# M710-9601.net
KiCad netlist of a schematic drawn in EAGLE
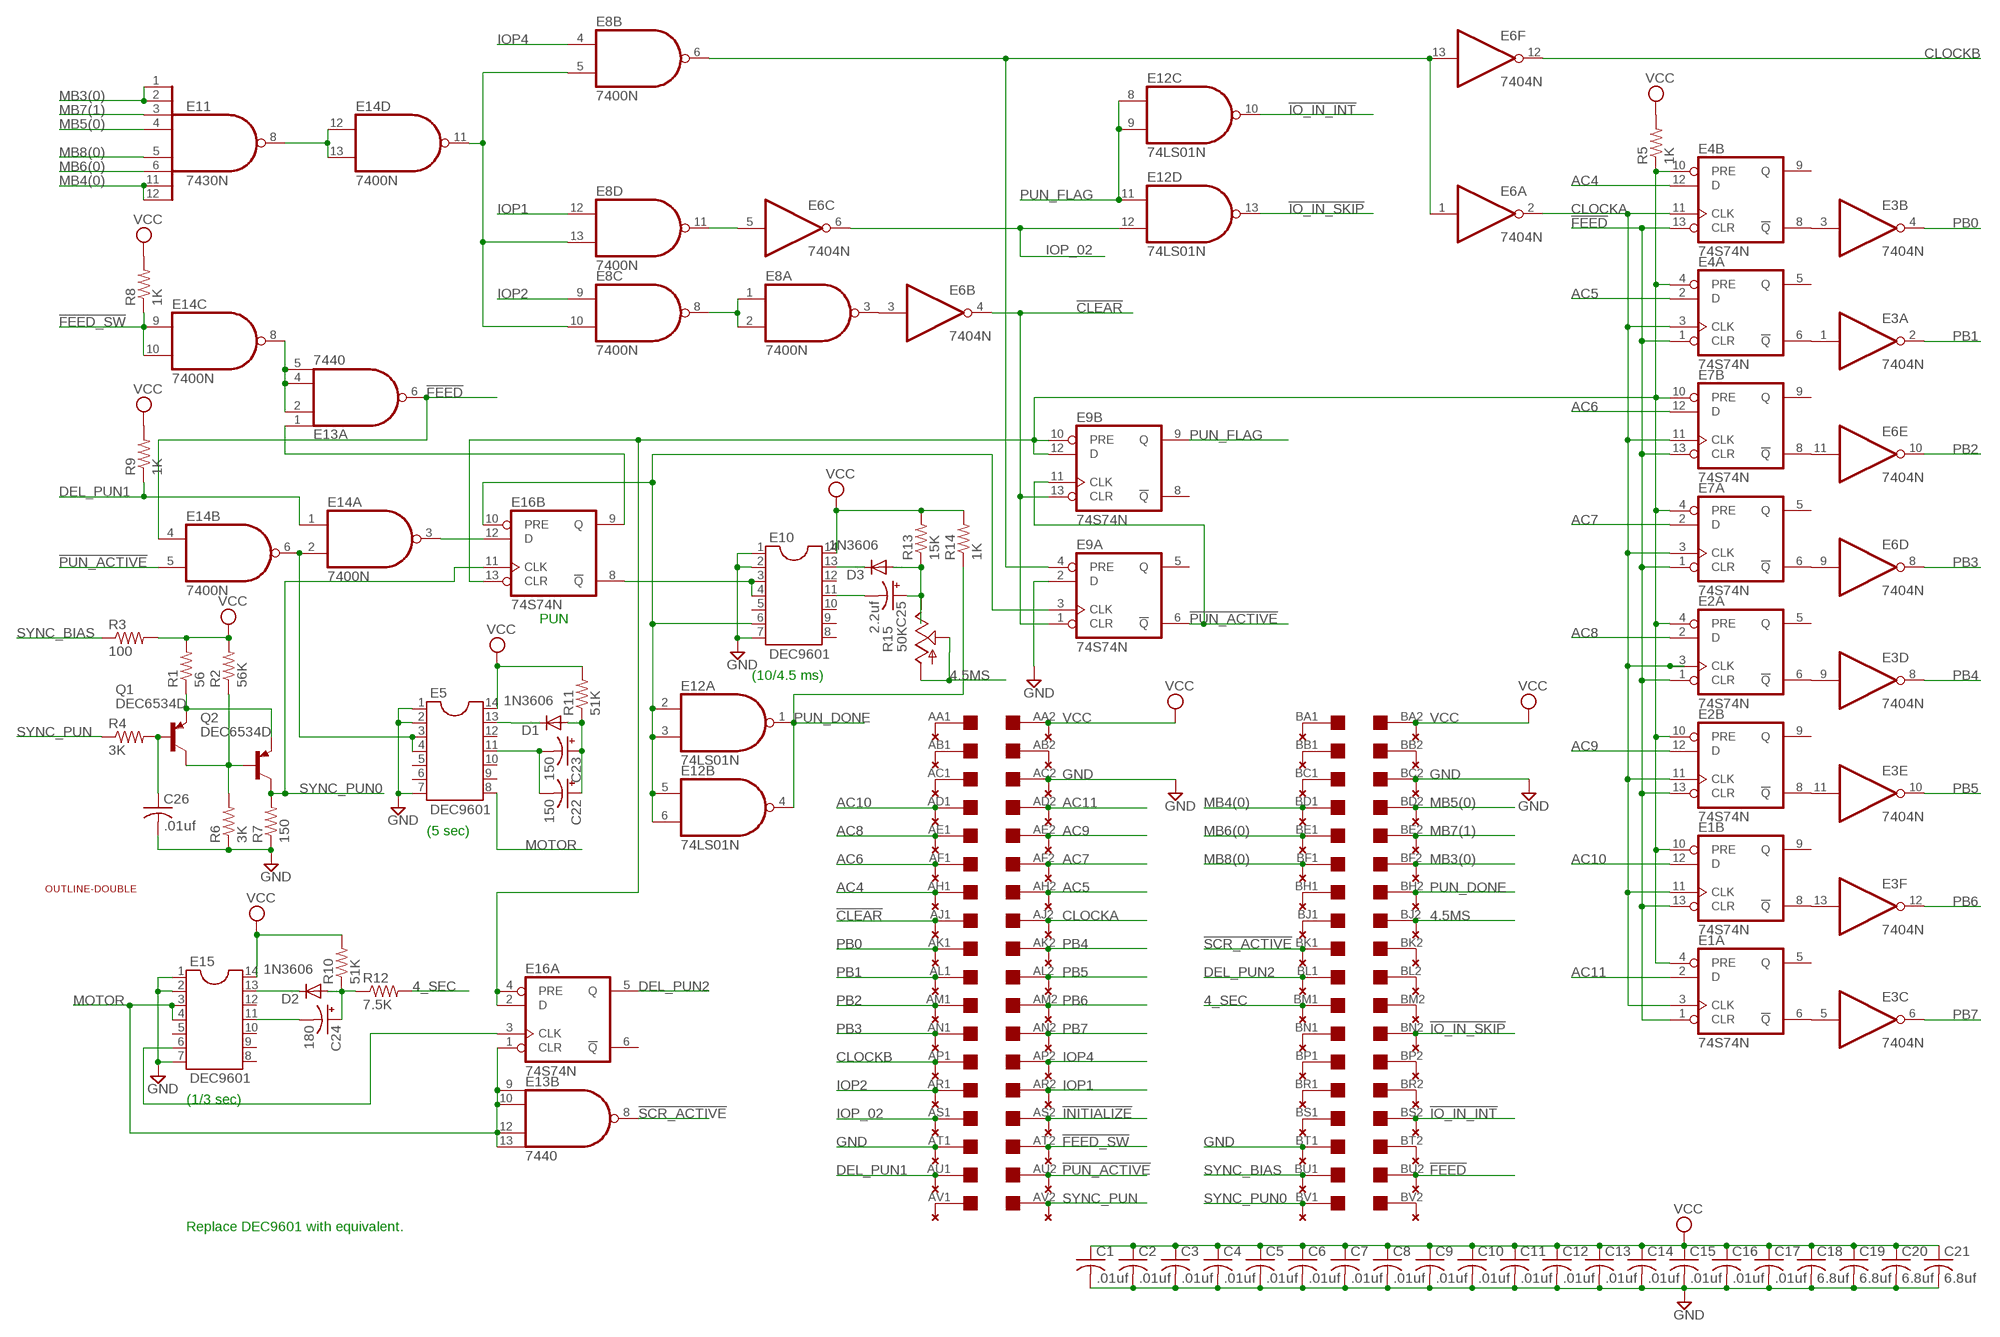
[diagram p0: schematic, sheet 1]

(export (version "E")
  (design (tool "Eeschema 10.0.6"))
  (components
    (comp (ref "C1")
      (value ".01uf")
      (footprint "eagle-import:C050-025X075")
      (libsource (lib "eagle-import") (part "C-US050-025X075"))
    )
    (comp (ref "C2")
      (value ".01uf")
      (footprint "eagle-import:C050-025X075")
      (libsource (lib "eagle-import") (part "C-US050-025X075"))
    )
    (comp (ref "C3")
      (value ".01uf")
      (footprint "eagle-import:C050-025X075")
      (libsource (lib "eagle-import") (part "C-US050-025X075"))
    )
    (comp (ref "C4")
      (value ".01uf")
      (footprint "eagle-import:C050-025X075")
      (libsource (lib "eagle-import") (part "C-US050-025X075"))
    )
    (comp (ref "C5")
      (value ".01uf")
      (footprint "eagle-import:C050-025X075")
      (libsource (lib "eagle-import") (part "C-US050-025X075"))
    )
    (comp (ref "C6")
      (value ".01uf")
      (footprint "eagle-import:C050-025X075")
      (libsource (lib "eagle-import") (part "C-US050-025X075"))
    )
    (comp (ref "C7")
      (value ".01uf")
      (footprint "eagle-import:C050-025X075")
      (libsource (lib "eagle-import") (part "C-US050-025X075"))
    )
    (comp (ref "C8")
      (value ".01uf")
      (footprint "eagle-import:C050-025X075")
      (libsource (lib "eagle-import") (part "C-US050-025X075"))
    )
    (comp (ref "C9")
      (value ".01uf")
      (footprint "eagle-import:C050-025X075")
      (libsource (lib "eagle-import") (part "C-US050-025X075"))
    )
    (comp (ref "C10")
      (value ".01uf")
      (footprint "eagle-import:C050-025X075")
      (libsource (lib "eagle-import") (part "C-US050-025X075"))
    )
    (comp (ref "C11")
      (value ".01uf")
      (footprint "eagle-import:C050-025X075")
      (libsource (lib "eagle-import") (part "C-US050-025X075"))
    )
    (comp (ref "C12")
      (value ".01uf")
      (footprint "eagle-import:C050-025X075")
      (libsource (lib "eagle-import") (part "C-US050-025X075"))
    )
    (comp (ref "C13")
      (value ".01uf")
      (footprint "eagle-import:C050-025X075")
      (libsource (lib "eagle-import") (part "C-US050-025X075"))
    )
    (comp (ref "C14")
      (value ".01uf")
      (footprint "eagle-import:C050-025X075")
      (libsource (lib "eagle-import") (part "C-US050-025X075"))
    )
    (comp (ref "C15")
      (value ".01uf")
      (footprint "eagle-import:C050-025X075")
      (libsource (lib "eagle-import") (part "C-US050-025X075"))
    )
    (comp (ref "C16")
      (value ".01uf")
      (footprint "eagle-import:C050-025X075")
      (libsource (lib "eagle-import") (part "C-US050-025X075"))
    )
    (comp (ref "C17")
      (value ".01uf")
      (footprint "eagle-import:C050-025X075")
      (libsource (lib "eagle-import") (part "C-US050-025X075"))
    )
    (comp (ref "C18")
      (value "6.8uf")
      (footprint "eagle-import:C150-054X183")
      (libsource (lib "eagle-import") (part "C-US150-054X183"))
    )
    (comp (ref "C19")
      (value "6.8uf")
      (footprint "eagle-import:C150-054X183")
      (libsource (lib "eagle-import") (part "C-US150-054X183"))
    )
    (comp (ref "C20")
      (value "6.8uf")
      (footprint "eagle-import:C150-054X183")
      (libsource (lib "eagle-import") (part "C-US150-054X183"))
    )
    (comp (ref "C21")
      (value "6.8uf")
      (footprint "eagle-import:C150-054X183")
      (libsource (lib "eagle-import") (part "C-US150-054X183"))
    )
    (comp (ref "C22")
      (value "150")
      (footprint "eagle-import:E5-8,5")
      (libsource (lib "eagle-import") (part "CPOL-USE5-8.5"))
    )
    (comp (ref "C23")
      (value "150")
      (footprint "eagle-import:E5-8,5")
      (libsource (lib "eagle-import") (part "CPOL-USE5-8.5"))
    )
    (comp (ref "C24")
      (value "180")
      (footprint "eagle-import:E5-8,5")
      (libsource (lib "eagle-import") (part "CPOL-USE5-8.5"))
    )
    (comp (ref "C25")
      (value "2.2uf")
      (footprint "eagle-import:E5-8,5")
      (libsource (lib "eagle-import") (part "CPOL-USE5-8.5"))
    )
    (comp (ref "C26")
      (value ".01uf")
      (footprint "eagle-import:C050-025X075")
      (libsource (lib "eagle-import") (part "C-US050-025X075"))
    )
    (comp (ref "D1")
      (value "1N3606")
      (footprint "eagle-import:DO41-10")
      (libsource (lib "eagle-import") (part "1N4004"))
    )
    (comp (ref "D2")
      (value "1N3606")
      (footprint "eagle-import:DO41-10")
      (libsource (lib "eagle-import") (part "1N4004"))
    )
    (comp (ref "D3")
      (value "1N3606")
      (footprint "eagle-import:DO41-10")
      (libsource (lib "eagle-import") (part "1N4004"))
    )
    (comp (ref "E1")
      (value "74S74N")
      (footprint "eagle-import:DIL14")
      (libsource (lib "eagle-import") (part "7474NS"))
    )
    (comp (ref "E2")
      (value "74S74N")
      (footprint "eagle-import:DIL14")
      (libsource (lib "eagle-import") (part "7474NS"))
    )
    (comp (ref "E3")
      (value "7404N")
      (footprint "eagle-import:DIL14")
      (libsource (lib "eagle-import") (part "7404N"))
    )
    (comp (ref "E4")
      (value "74S74N")
      (footprint "eagle-import:DIL14")
      (libsource (lib "eagle-import") (part "7474NS"))
    )
    (comp (ref "E5")
      (value "DEC9601")
      (footprint "eagle-import:DIL14")
      (libsource (lib "eagle-import") (part "DIL14"))
    )
    (comp (ref "E6")
      (value "7404N")
      (footprint "eagle-import:DIL14")
      (libsource (lib "eagle-import") (part "7404N"))
    )
    (comp (ref "E7")
      (value "74S74N")
      (footprint "eagle-import:DIL14")
      (libsource (lib "eagle-import") (part "7474NS"))
    )
    (comp (ref "E8")
      (value "7400N")
      (footprint "eagle-import:DIL14")
      (libsource (lib "eagle-import") (part "7400N"))
    )
    (comp (ref "E9")
      (value "74S74N")
      (footprint "eagle-import:DIL14")
      (libsource (lib "eagle-import") (part "7474NS"))
    )
    (comp (ref "E10")
      (value "DEC9601")
      (footprint "eagle-import:DIL14")
      (libsource (lib "eagle-import") (part "DIL14"))
    )
    (comp (ref "E11")
      (value "7430N")
      (footprint "eagle-import:DIL14")
      (libsource (lib "eagle-import") (part "7430N"))
    )
    (comp (ref "E12")
      (value "74LS01N")
      (footprint "eagle-import:DIL14")
      (libsource (lib "eagle-import") (part "7401NLS"))
    )
    (comp (ref "E13")
      (value "7440")
      (footprint "eagle-import:DIL14")
      (libsource (lib "eagle-import") (part "7420NS"))
    )
    (comp (ref "E14")
      (value "7400N")
      (footprint "eagle-import:DIL14")
      (libsource (lib "eagle-import") (part "7400N"))
    )
    (comp (ref "E15")
      (value "DEC9601")
      (footprint "eagle-import:DIL14")
      (libsource (lib "eagle-import") (part "DIL14"))
    )
    (comp (ref "E16")
      (value "74S74N")
      (footprint "eagle-import:DIL14")
      (libsource (lib "eagle-import") (part "7474NS"))
    )
    (comp (ref "Q1")
      (value "DEC6534D")
      (footprint "eagle-import:TO92")
      (libsource (lib "eagle-import") (part "2N3906"))
    )
    (comp (ref "Q2")
      (value "DEC6534D")
      (footprint "eagle-import:TO92")
      (libsource (lib "eagle-import") (part "2N3906"))
    )
    (comp (ref "R1")
      (value "56")
      (footprint "eagle-import:0207_7")
      (libsource (lib "eagle-import") (part "R-US_0207/7"))
    )
    (comp (ref "R2")
      (value "56K")
      (footprint "eagle-import:0207_7")
      (libsource (lib "eagle-import") (part "R-US_0207/7"))
    )
    (comp (ref "R3")
      (value "100")
      (footprint "eagle-import:0207_7")
      (libsource (lib "eagle-import") (part "R-US_0207/7"))
    )
    (comp (ref "R4")
      (value "3K")
      (footprint "eagle-import:0207_7")
      (libsource (lib "eagle-import") (part "R-US_0207/7"))
    )
    (comp (ref "R5")
      (value "1K")
      (footprint "eagle-import:0207_7")
      (libsource (lib "eagle-import") (part "R-US_0207/7"))
    )
    (comp (ref "R6")
      (value "3K")
      (footprint "eagle-import:0207_7")
      (libsource (lib "eagle-import") (part "R-US_0207/7"))
    )
    (comp (ref "R7")
      (value "150")
      (footprint "eagle-import:0207_7")
      (libsource (lib "eagle-import") (part "R-US_0207/7"))
    )
    (comp (ref "R8")
      (value "1K")
      (footprint "eagle-import:0207_7")
      (libsource (lib "eagle-import") (part "R-US_0207/7"))
    )
    (comp (ref "R9")
      (value "1K")
      (footprint "eagle-import:0207_7")
      (libsource (lib "eagle-import") (part "R-US_0207/7"))
    )
    (comp (ref "R10")
      (value "51K")
      (footprint "eagle-import:0207_7")
      (libsource (lib "eagle-import") (part "R-US_0207/7"))
    )
    (comp (ref "R11")
      (value "51K")
      (footprint "eagle-import:0207_7")
      (libsource (lib "eagle-import") (part "R-US_0207/7"))
    )
    (comp (ref "R12")
      (value "7.5K")
      (footprint "eagle-import:0207_7")
      (libsource (lib "eagle-import") (part "R-US_0207/7"))
    )
    (comp (ref "R13")
      (value "15K")
      (footprint "eagle-import:0207_7")
      (libsource (lib "eagle-import") (part "R-US_0207/7"))
    )
    (comp (ref "R14")
      (value "1K")
      (footprint "eagle-import:0207_7")
      (libsource (lib "eagle-import") (part "R-US_0207/7"))
    )
    (comp (ref "R15")
      (value "50K")
      (footprint "eagle-import:PT-SPIN")
      (libsource (lib "eagle-import") (part "TRIM_US-PTSPIN"))
    )
    (comp (ref "U$1")
      (value "OUTLINE-DOUBLE")
      (footprint "eagle-import:DOUBLE")
      (libsource (lib "eagle-import") (part "OUTLINE-DOUBLE"))
    )
    (comp (ref "U$2")
      (value "DOUBLE")
      (footprint "eagle-import:EDGE-CON4")
      (libsource (lib "eagle-import") (part "DOUBLE"))
    )
    (comp (ref "U$5")
      (value "THRU-HOLE2B")
      (footprint "eagle-import:THRU-HOLEB")
      (libsource (lib "eagle-import") (part "THRU-HOLE2B"))
    )
    (comp (ref "U$7")
      (value "THRU-HOLE2B")
      (footprint "eagle-import:THRU-HOLEB")
      (libsource (lib "eagle-import") (part "THRU-HOLE2B"))
    )
  )
  (nets
    (net (code "1") (name "/4.5MS") (class "Default")
      (node (ref "R15") (pin "A") (pinfunction "A_A") (pintype "passive"))
      (node (ref "R15") (pin "S") (pinfunction "S_S") (pintype "passive"))
      (node (ref "U$2") (pin "BJ2") (pinfunction "1_BJ2") (pintype "bidirectional"))
      (node (ref "U$5") (pin "J2") (pinfunction "P$1_J2") (pintype "passive"))
    )
    (net (code "2") (name "/4_SEC") (class "Default")
      (node (ref "R12") (pin "2") (pinfunction "2_2") (pintype "passive"))
      (node (ref "U$2") (pin "BM1") (pinfunction "1_BM1") (pintype "bidirectional"))
      (node (ref "U$5") (pin "M1") (pinfunction "P$1_M1") (pintype "passive"))
    )
    (net (code "3") (name "/AC4") (class "Default")
      (node (ref "E4") (pin "12") (pinfunction "D_12") (pintype "input"))
      (node (ref "U$2") (pin "AH1") (pinfunction "1_AH1") (pintype "bidirectional"))
      (node (ref "U$7") (pin "H1") (pinfunction "P$1_H1") (pintype "passive"))
    )
    (net (code "4") (name "/AC5") (class "Default")
      (node (ref "E4") (pin "2") (pinfunction "D_2") (pintype "input"))
      (node (ref "U$2") (pin "AH2") (pinfunction "1_AH2") (pintype "bidirectional"))
      (node (ref "U$7") (pin "H2") (pinfunction "P$1_H2") (pintype "passive"))
    )
    (net (code "5") (name "/AC6") (class "Default")
      (node (ref "E7") (pin "12") (pinfunction "D_12") (pintype "input"))
      (node (ref "U$2") (pin "AF1") (pinfunction "1_AF1") (pintype "bidirectional"))
      (node (ref "U$7") (pin "F1") (pinfunction "P$1_F1") (pintype "passive"))
    )
    (net (code "6") (name "/AC7") (class "Default")
      (node (ref "E7") (pin "2") (pinfunction "D_2") (pintype "input"))
      (node (ref "U$2") (pin "AF2") (pinfunction "1_AF2") (pintype "bidirectional"))
      (node (ref "U$7") (pin "F2") (pinfunction "P$1_F2") (pintype "passive"))
    )
    (net (code "7") (name "/AC8") (class "Default")
      (node (ref "E2") (pin "2") (pinfunction "D_2") (pintype "input"))
      (node (ref "U$2") (pin "AE1") (pinfunction "1_AE1") (pintype "bidirectional"))
      (node (ref "U$7") (pin "E1") (pinfunction "P$1_E1") (pintype "passive"))
    )
    (net (code "8") (name "/AC9") (class "Default")
      (node (ref "E2") (pin "12") (pinfunction "D_12") (pintype "input"))
      (node (ref "U$2") (pin "AE2") (pinfunction "1_AE2") (pintype "bidirectional"))
      (node (ref "U$7") (pin "E2") (pinfunction "P$1_E2") (pintype "passive"))
    )
    (net (code "9") (name "/AC10") (class "Default")
      (node (ref "E1") (pin "12") (pinfunction "D_12") (pintype "input"))
      (node (ref "U$2") (pin "AD1") (pinfunction "1_AD1") (pintype "bidirectional"))
      (node (ref "U$7") (pin "D1") (pinfunction "P$1_D1") (pintype "passive"))
    )
    (net (code "10") (name "/AC11") (class "Default")
      (node (ref "E1") (pin "2") (pinfunction "D_2") (pintype "input"))
      (node (ref "U$2") (pin "AD2") (pinfunction "1_AD2") (pintype "bidirectional"))
      (node (ref "U$7") (pin "D2") (pinfunction "P$1_D2") (pintype "passive"))
    )
    (net (code "11") (name "/CLOCKA") (class "Default")
      (node (ref "E1") (pin "11") (pinfunction "CLK_11") (pintype "input"))
      (node (ref "E1") (pin "3") (pinfunction "CLK_3") (pintype "input"))
      (node (ref "E2") (pin "11") (pinfunction "CLK_11") (pintype "input"))
      (node (ref "E2") (pin "3") (pinfunction "CLK_3") (pintype "input"))
      (node (ref "E4") (pin "11") (pinfunction "CLK_11") (pintype "input"))
      (node (ref "E4") (pin "3") (pinfunction "CLK_3") (pintype "input"))
      (node (ref "E6") (pin "2") (pinfunction "O_2") (pintype "output"))
      (node (ref "E7") (pin "11") (pinfunction "CLK_11") (pintype "input"))
      (node (ref "E7") (pin "3") (pinfunction "CLK_3") (pintype "input"))
      (node (ref "U$2") (pin "AJ2") (pinfunction "1_AJ2") (pintype "bidirectional"))
      (node (ref "U$7") (pin "J2") (pinfunction "P$1_J2") (pintype "passive"))
    )
    (net (code "12") (name "/CLOCKB") (class "Default")
      (node (ref "E6") (pin "12") (pinfunction "O_12") (pintype "output"))
      (node (ref "U$2") (pin "AP1") (pinfunction "1_AP1") (pintype "bidirectional"))
      (node (ref "U$7") (pin "P1") (pinfunction "P$1_P1") (pintype "passive"))
    )
    (net (code "13") (name "/DEL_PUN1") (class "Default")
      (node (ref "E14") (pin "1") (pinfunction "I0_1") (pintype "input"))
      (node (ref "R9") (pin "1") (pinfunction "1_1") (pintype "passive"))
      (node (ref "U$2") (pin "AU1") (pinfunction "1_AU1") (pintype "bidirectional"))
      (node (ref "U$7") (pin "U1") (pinfunction "P$1_U1") (pintype "passive"))
    )
    (net (code "14") (name "/DEL_PUN2") (class "Default")
      (node (ref "E16") (pin "5") (pinfunction "Q_5") (pintype "output"))
      (node (ref "U$2") (pin "BL1") (pinfunction "1_BL1") (pintype "bidirectional"))
      (node (ref "U$5") (pin "L1") (pinfunction "P$1_L1") (pintype "passive"))
    )
    (net (code "15") (name "/IOP1") (class "Default")
      (node (ref "E8") (pin "12") (pinfunction "I0_12") (pintype "input"))
      (node (ref "U$2") (pin "AR2") (pinfunction "1_AR2") (pintype "bidirectional"))
      (node (ref "U$7") (pin "R2") (pinfunction "P$1_R2") (pintype "passive"))
    )
    (net (code "16") (name "/IOP2") (class "Default")
      (node (ref "E8") (pin "9") (pinfunction "I0_9") (pintype "input"))
      (node (ref "U$2") (pin "AR1") (pinfunction "1_AR1") (pintype "bidirectional"))
      (node (ref "U$7") (pin "R1") (pinfunction "P$1_R1") (pintype "passive"))
    )
    (net (code "17") (name "/IOP4") (class "Default")
      (node (ref "E8") (pin "4") (pinfunction "I0_4") (pintype "input"))
      (node (ref "U$2") (pin "AP2") (pinfunction "1_AP2") (pintype "bidirectional"))
      (node (ref "U$7") (pin "P2") (pinfunction "P$1_P2") (pintype "passive"))
    )
    (net (code "18") (name "/IOP_02") (class "Default")
      (node (ref "E12") (pin "12") (pinfunction "I1_12") (pintype "input"))
      (node (ref "E6") (pin "6") (pinfunction "O_6") (pintype "output"))
      (node (ref "U$2") (pin "AS1") (pinfunction "1_AS1") (pintype "bidirectional"))
      (node (ref "U$7") (pin "S1") (pinfunction "P$1_S1") (pintype "passive"))
    )
    (net (code "19") (name "/MB3(0)") (class "Default")
      (node (ref "E11") (pin "1") (pinfunction "I0_1") (pintype "input"))
      (node (ref "E11") (pin "2") (pinfunction "I1_2") (pintype "input"))
      (node (ref "U$2") (pin "BF2") (pinfunction "1_BF2") (pintype "bidirectional"))
      (node (ref "U$5") (pin "F2") (pinfunction "P$1_F2") (pintype "passive"))
    )
    (net (code "20") (name "/MB4(0)") (class "Default")
      (node (ref "E11") (pin "11") (pinfunction "I6_11") (pintype "input"))
      (node (ref "E11") (pin "12") (pinfunction "I7_12") (pintype "input"))
      (node (ref "U$2") (pin "BD1") (pinfunction "1_BD1") (pintype "bidirectional"))
      (node (ref "U$5") (pin "D1") (pinfunction "P$1_D1") (pintype "passive"))
    )
    (net (code "21") (name "/MB5(0)") (class "Default")
      (node (ref "E11") (pin "4") (pinfunction "I3_4") (pintype "input"))
      (node (ref "U$2") (pin "BD2") (pinfunction "1_BD2") (pintype "bidirectional"))
      (node (ref "U$5") (pin "D2") (pinfunction "P$1_D2") (pintype "passive"))
    )
    (net (code "22") (name "/MB6(0)") (class "Default")
      (node (ref "E11") (pin "6") (pinfunction "I5_6") (pintype "input"))
      (node (ref "U$2") (pin "BE1") (pinfunction "1_BE1") (pintype "bidirectional"))
      (node (ref "U$5") (pin "E1") (pinfunction "P$1_E1") (pintype "passive"))
    )
    (net (code "23") (name "/MB7(1)") (class "Default")
      (node (ref "E11") (pin "3") (pinfunction "I2_3") (pintype "input"))
      (node (ref "U$2") (pin "BE2") (pinfunction "1_BE2") (pintype "bidirectional"))
      (node (ref "U$5") (pin "E2") (pinfunction "P$1_E2") (pintype "passive"))
    )
    (net (code "24") (name "/MB8(0)") (class "Default")
      (node (ref "E11") (pin "5") (pinfunction "I4_5") (pintype "input"))
      (node (ref "U$2") (pin "BF1") (pinfunction "1_BF1") (pintype "bidirectional"))
      (node (ref "U$5") (pin "F1") (pinfunction "P$1_F1") (pintype "passive"))
    )
    (net (code "25") (name "/MOTOR") (class "Default")
      (node (ref "E13") (pin "10") (pinfunction "I1_10") (pintype "input"))
      (node (ref "E13") (pin "12") (pinfunction "I2_12") (pintype "input"))
      (node (ref "E13") (pin "13") (pinfunction "I3_13") (pintype "input"))
      (node (ref "E13") (pin "9") (pinfunction "I0_9") (pintype "input"))
      (node (ref "E15") (pin "3") (pinfunction "3_3") (pintype "passive"))
      (node (ref "E15") (pin "4") (pinfunction "4_4") (pintype "passive"))
      (node (ref "E16") (pin "1") (pinfunction "CLR_1") (pintype "input"))
      (node (ref "E5") (pin "8") (pinfunction "8_8") (pintype "passive"))
    )
    (net (code "26") (name "/PB0") (class "Default")
      (node (ref "E3") (pin "4") (pinfunction "O_4") (pintype "output"))
      (node (ref "U$2") (pin "AK1") (pinfunction "1_AK1") (pintype "bidirectional"))
      (node (ref "U$7") (pin "K1") (pinfunction "P$1_K1") (pintype "passive"))
    )
    (net (code "27") (name "/PB1") (class "Default")
      (node (ref "E3") (pin "2") (pinfunction "O_2") (pintype "output"))
      (node (ref "U$2") (pin "AL1") (pinfunction "1_AL1") (pintype "bidirectional"))
      (node (ref "U$7") (pin "L1") (pinfunction "P$1_L1") (pintype "passive"))
    )
    (net (code "28") (name "/PB2") (class "Default")
      (node (ref "E6") (pin "10") (pinfunction "O_10") (pintype "output"))
      (node (ref "U$2") (pin "AM1") (pinfunction "1_AM1") (pintype "bidirectional"))
      (node (ref "U$7") (pin "M1") (pinfunction "P$1_M1") (pintype "passive"))
    )
    (net (code "29") (name "/PB3") (class "Default")
      (node (ref "E6") (pin "8") (pinfunction "O_8") (pintype "output"))
      (node (ref "U$2") (pin "AN1") (pinfunction "1_AN1") (pintype "bidirectional"))
      (node (ref "U$7") (pin "N1") (pinfunction "P$1_N1") (pintype "passive"))
    )
    (net (code "30") (name "/PB4") (class "Default")
      (node (ref "E3") (pin "8") (pinfunction "O_8") (pintype "output"))
      (node (ref "U$2") (pin "AK2") (pinfunction "1_AK2") (pintype "bidirectional"))
      (node (ref "U$7") (pin "K2") (pinfunction "P$1_K2") (pintype "passive"))
    )
    (net (code "31") (name "/PB5") (class "Default")
      (node (ref "E3") (pin "10") (pinfunction "O_10") (pintype "output"))
      (node (ref "U$2") (pin "AL2") (pinfunction "1_AL2") (pintype "bidirectional"))
      (node (ref "U$7") (pin "L2") (pinfunction "P$1_L2") (pintype "passive"))
    )
    (net (code "32") (name "/PB6") (class "Default")
      (node (ref "E3") (pin "12") (pinfunction "O_12") (pintype "output"))
      (node (ref "U$2") (pin "AM2") (pinfunction "1_AM2") (pintype "bidirectional"))
      (node (ref "U$7") (pin "M2") (pinfunction "P$1_M2") (pintype "passive"))
    )
    (net (code "33") (name "/PB7") (class "Default")
      (node (ref "E3") (pin "6") (pinfunction "O_6") (pintype "output"))
      (node (ref "U$2") (pin "AN2") (pinfunction "1_AN2") (pintype "bidirectional"))
      (node (ref "U$7") (pin "N2") (pinfunction "P$1_N2") (pintype "passive"))
    )
    (net (code "34") (name "/PUN_DONE") (class "Default")
      (node (ref "E12") (pin "1") (pinfunction "O_1") (pintype "open_collector"))
      (node (ref "E12") (pin "4") (pinfunction "O_4") (pintype "open_collector"))
      (node (ref "R14") (pin "1") (pinfunction "1_1") (pintype "passive"))
      (node (ref "U$2") (pin "BH2") (pinfunction "1_BH2") (pintype "bidirectional"))
      (node (ref "U$5") (pin "H2") (pinfunction "P$1_H2") (pintype "passive"))
    )
    (net (code "35") (name "/PUN_FLAG") (class "Default")
      (node (ref "E12") (pin "11") (pinfunction "I0_11") (pintype "input"))
      (node (ref "E12") (pin "8") (pinfunction "I0_8") (pintype "input"))
      (node (ref "E12") (pin "9") (pinfunction "I1_9") (pintype "input"))
      (node (ref "E9") (pin "9") (pinfunction "Q_9") (pintype "output"))
    )
    (net (code "36") (name "/SYNC_BIAS") (class "Default")
      (node (ref "R3") (pin "1") (pinfunction "1_1") (pintype "passive"))
      (node (ref "U$2") (pin "BU1") (pinfunction "1_BU1") (pintype "bidirectional"))
      (node (ref "U$5") (pin "U1") (pinfunction "P$1_U1") (pintype "passive"))
    )
    (net (code "37") (name "/SYNC_PUN") (class "Default")
      (node (ref "R4") (pin "1") (pinfunction "1_1") (pintype "passive"))
      (node (ref "U$2") (pin "AV2") (pinfunction "1_AV2") (pintype "bidirectional"))
      (node (ref "U$7") (pin "V2") (pinfunction "P$1_V2") (pintype "passive"))
    )
    (net (code "38") (name "/SYNC_PUN0") (class "Default")
      (node (ref "E16") (pin "11") (pinfunction "CLK_11") (pintype "input"))
      (node (ref "Q2") (pin "1") (pinfunction "C_1") (pintype "passive"))
      (node (ref "R7") (pin "2") (pinfunction "2_2") (pintype "passive"))
      (node (ref "U$2") (pin "BV1") (pinfunction "1_BV1") (pintype "bidirectional"))
      (node (ref "U$5") (pin "V1") (pinfunction "P$1_V1") (pintype "passive"))
    )
    (net (code "39") (name "/~{CLEAR}") (class "Default")
      (node (ref "E6") (pin "4") (pinfunction "O_4") (pintype "output"))
      (node (ref "E9") (pin "1") (pinfunction "CLR_1") (pintype "input"))
      (node (ref "E9") (pin "13") (pinfunction "CLR_13") (pintype "input"))
      (node (ref "U$2") (pin "AJ1") (pinfunction "1_AJ1") (pintype "bidirectional"))
      (node (ref "U$7") (pin "J1") (pinfunction "P$1_J1") (pintype "passive"))
    )
    (net (code "40") (name "/~{FEED_SW}") (class "Default")
      (node (ref "E14") (pin "10") (pinfunction "I1_10") (pintype "input"))
      (node (ref "E14") (pin "9") (pinfunction "I0_9") (pintype "input"))
      (node (ref "R8") (pin "1") (pinfunction "1_1") (pintype "passive"))
      (node (ref "U$2") (pin "AT2") (pinfunction "1_AT2") (pintype "bidirectional"))
      (node (ref "U$7") (pin "T2") (pinfunction "P$1_T2") (pintype "passive"))
    )
    (net (code "41") (name "/~{FEED}") (class "Default")
      (node (ref "E1") (pin "1") (pinfunction "CLR_1") (pintype "input"))
      (node (ref "E1") (pin "13") (pinfunction "CLR_13") (pintype "input"))
      (node (ref "E13") (pin "6") (pinfunction "O_6") (pintype "output"))
      (node (ref "E14") (pin "4") (pinfunction "I0_4") (pintype "input"))
      (node (ref "E2") (pin "1") (pinfunction "CLR_1") (pintype "input"))
      (node (ref "E2") (pin "13") (pinfunction "CLR_13") (pintype "input"))
      (node (ref "E4") (pin "1") (pinfunction "CLR_1") (pintype "input"))
      (node (ref "E4") (pin "13") (pinfunction "CLR_13") (pintype "input"))
      (node (ref "E7") (pin "1") (pinfunction "CLR_1") (pintype "input"))
      (node (ref "E7") (pin "13") (pinfunction "CLR_13") (pintype "input"))
      (node (ref "U$2") (pin "BU2") (pinfunction "1_BU2") (pintype "bidirectional"))
      (node (ref "U$5") (pin "U2") (pinfunction "P$1_U2") (pintype "passive"))
    )
    (net (code "42") (name "/~{INITIALIZE}") (class "Default")
      (node (ref "U$2") (pin "AS2") (pinfunction "1_AS2") (pintype "bidirectional"))
      (node (ref "U$7") (pin "S2") (pinfunction "P$1_S2") (pintype "passive"))
    )
    (net (code "43") (name "/~{IO_IN_INT}") (class "Default")
      (node (ref "E12") (pin "10") (pinfunction "O_10") (pintype "open_collector"))
      (node (ref "U$2") (pin "BS2") (pinfunction "1_BS2") (pintype "bidirectional"))
      (node (ref "U$5") (pin "S2") (pinfunction "P$1_S2") (pintype "passive"))
    )
    (net (code "44") (name "/~{IO_IN_SKIP}") (class "Default")
      (node (ref "E12") (pin "13") (pinfunction "O_13") (pintype "open_collector"))
      (node (ref "U$2") (pin "BN2") (pinfunction "1_BN2") (pintype "bidirectional"))
      (node (ref "U$5") (pin "N2") (pinfunction "P$1_N2") (pintype "passive"))
    )
    (net (code "45") (name "/~{PUN_ACTIVE}") (class "Default")
      (node (ref "E14") (pin "5") (pinfunction "I1_5") (pintype "input"))
      (node (ref "E9") (pin "11") (pinfunction "CLK_11") (pintype "input"))
      (node (ref "E9") (pin "6") (pinfunction "~{Q}_6") (pintype "output"))
      (node (ref "U$2") (pin "AU2") (pinfunction "1_AU2") (pintype "bidirectional"))
      (node (ref "U$7") (pin "U2") (pinfunction "P$1_U2") (pintype "passive"))
    )
    (net (code "46") (name "/~{SCR_ACTIVE}") (class "Default")
      (node (ref "E13") (pin "8") (pinfunction "O_8") (pintype "output"))
      (node (ref "U$2") (pin "BK1") (pinfunction "1_BK1") (pintype "bidirectional"))
      (node (ref "U$5") (pin "K1") (pinfunction "P$1_K1") (pintype "passive"))
    )
    (net (code "47") (name "GND") (class "Default")
      (node (ref "C1") (pin "2") (pinfunction "2_2") (pintype "passive"))
      (node (ref "C10") (pin "2") (pinfunction "2_2") (pintype "passive"))
      (node (ref "C11") (pin "2") (pinfunction "2_2") (pintype "passive"))
      (node (ref "C12") (pin "2") (pinfunction "2_2") (pintype "passive"))
      (node (ref "C13") (pin "2") (pinfunction "2_2") (pintype "passive"))
      (node (ref "C14") (pin "2") (pinfunction "2_2") (pintype "passive"))
      (node (ref "C15") (pin "2") (pinfunction "2_2") (pintype "passive"))
      (node (ref "C16") (pin "2") (pinfunction "2_2") (pintype "passive"))
      (node (ref "C17") (pin "2") (pinfunction "2_2") (pintype "passive"))
      (node (ref "C18") (pin "2") (pinfunction "2_2") (pintype "passive"))
      (node (ref "C19") (pin "2") (pinfunction "2_2") (pintype "passive"))
      (node (ref "C2") (pin "2") (pinfunction "2_2") (pintype "passive"))
      (node (ref "C20") (pin "2") (pinfunction "2_2") (pintype "passive"))
      (node (ref "C21") (pin "2") (pinfunction "2_2") (pintype "passive"))
      (node (ref "C26") (pin "2") (pinfunction "2_2") (pintype "passive"))
      (node (ref "C3") (pin "2") (pinfunction "2_2") (pintype "passive"))
      (node (ref "C4") (pin "2") (pinfunction "2_2") (pintype "passive"))
      (node (ref "C5") (pin "2") (pinfunction "2_2") (pintype "passive"))
      (node (ref "C6") (pin "2") (pinfunction "2_2") (pintype "passive"))
      (node (ref "C7") (pin "2") (pinfunction "2_2") (pintype "passive"))
      (node (ref "C8") (pin "2") (pinfunction "2_2") (pintype "passive"))
      (node (ref "C9") (pin "2") (pinfunction "2_2") (pintype "passive"))
      (node (ref "E10") (pin "1") (pinfunction "1_1") (pintype "passive"))
      (node (ref "E10") (pin "2") (pinfunction "2_2") (pintype "passive"))
      (node (ref "E10") (pin "7") (pinfunction "7_7") (pintype "passive"))
      (node (ref "E15") (pin "1") (pinfunction "1_1") (pintype "passive"))
      (node (ref "E15") (pin "2") (pinfunction "2_2") (pintype "passive"))
      (node (ref "E15") (pin "7") (pinfunction "7_7") (pintype "passive"))
      (node (ref "E5") (pin "1") (pinfunction "1_1") (pintype "passive"))
      (node (ref "E5") (pin "2") (pinfunction "2_2") (pintype "passive"))
      (node (ref "E5") (pin "7") (pinfunction "7_7") (pintype "passive"))
      (node (ref "E9") (pin "2") (pinfunction "D_2") (pintype "input"))
      (node (ref "R6") (pin "1") (pinfunction "1_1") (pintype "passive"))
      (node (ref "R7") (pin "1") (pinfunction "1_1") (pintype "passive"))
      (node (ref "U$2") (pin "AC2") (pinfunction "1_AC2") (pintype "bidirectional"))
      (node (ref "U$2") (pin "AT1") (pinfunction "1_AT1") (pintype "bidirectional"))
      (node (ref "U$2") (pin "BC2") (pinfunction "1_BC2") (pintype "bidirectional"))
      (node (ref "U$2") (pin "BT1") (pinfunction "1_BT1") (pintype "bidirectional"))
      (node (ref "U$5") (pin "C2") (pinfunction "P$1_C2") (pintype "passive"))
      (node (ref "U$5") (pin "T1") (pinfunction "P$1_T1") (pintype "passive"))
      (node (ref "U$7") (pin "C2") (pinfunction "P$1_C2") (pintype "passive"))
      (node (ref "U$7") (pin "T1") (pinfunction "P$1_T1") (pintype "passive"))
    )
    (net (code "48") (name "Net-(C22-Pad+)") (class "Default")
      (node (ref "C22") (pin "+") (pinfunction "+_+") (pintype "passive"))
      (node (ref "C23") (pin "+") (pinfunction "+_+") (pintype "passive"))
      (node (ref "D1") (pin "A") (pinfunction "A_A") (pintype "passive"))
      (node (ref "R11") (pin "1") (pinfunction "1_1") (pintype "passive"))
    )
    (net (code "49") (name "Net-(C22-Pad-)") (class "Default")
      (node (ref "C22") (pin "-") (pinfunction "-_-") (pintype "passive"))
      (node (ref "C23") (pin "-") (pinfunction "-_-") (pintype "passive"))
      (node (ref "E5") (pin "11") (pinfunction "11_11") (pintype "passive"))
    )
    (net (code "50") (name "Net-(C24-Pad+)") (class "Default")
      (node (ref "C24") (pin "+") (pinfunction "+_+") (pintype "passive"))
      (node (ref "D2") (pin "A") (pinfunction "A_A") (pintype "passive"))
      (node (ref "R10") (pin "1") (pinfunction "1_1") (pintype "passive"))
      (node (ref "R12") (pin "1") (pinfunction "1_1") (pintype "passive"))
    )
    (net (code "51") (name "Net-(C24-Pad-)") (class "Default")
      (node (ref "C24") (pin "-") (pinfunction "-_-") (pintype "passive"))
      (node (ref "E15") (pin "11") (pinfunction "11_11") (pintype "passive"))
    )
    (net (code "52") (name "Net-(C25-Pad+)") (class "Default")
      (node (ref "C25") (pin "+") (pinfunction "+_+") (pintype "passive"))
      (node (ref "D3") (pin "A") (pinfunction "A_A") (pintype "passive"))
      (node (ref "R13") (pin "1") (pinfunction "1_1") (pintype "passive"))
      (node (ref "R15") (pin "E") (pinfunction "E_E") (pintype "passive"))
    )
    (net (code "53") (name "Net-(C25-Pad-)") (class "Default")
      (node (ref "C25") (pin "-") (pinfunction "-_-") (pintype "passive"))
      (node (ref "E10") (pin "11") (pinfunction "11_11") (pintype "passive"))
    )
    (net (code "54") (name "Net-(D1-PadC)") (class "Default")
      (node (ref "D1") (pin "C") (pinfunction "C_C") (pintype "passive"))
      (node (ref "E5") (pin "13") (pinfunction "13_13") (pintype "passive"))
    )
    (net (code "55") (name "Net-(D2-PadC)") (class "Default")
      (node (ref "D2") (pin "C") (pinfunction "C_C") (pintype "passive"))
      (node (ref "E15") (pin "13") (pinfunction "13_13") (pintype "passive"))
    )
    (net (code "56") (name "Net-(D3-PadC)") (class "Default")
      (node (ref "D3") (pin "C") (pinfunction "C_C") (pintype "passive"))
      (node (ref "E10") (pin "13") (pinfunction "13_13") (pintype "passive"))
    )
    (net (code "57") (name "Net-(E1A-~{Q})") (class "Default")
      (node (ref "E1") (pin "6") (pinfunction "~{Q}_6") (pintype "output"))
      (node (ref "E3") (pin "5") (pinfunction "I_5") (pintype "input"))
    )
    (net (code "58") (name "Net-(E1B-~{Q})") (class "Default")
      (node (ref "E1") (pin "8") (pinfunction "~{Q}_8") (pintype "output"))
      (node (ref "E3") (pin "13") (pinfunction "I_13") (pintype "input"))
    )
    (net (code "59") (name "Net-(E2A-~{Q})") (class "Default")
      (node (ref "E2") (pin "6") (pinfunction "~{Q}_6") (pintype "output"))
      (node (ref "E3") (pin "9") (pinfunction "I_9") (pintype "input"))
    )
    (net (code "60") (name "Net-(E2B-~{Q})") (class "Default")
      (node (ref "E2") (pin "8") (pinfunction "~{Q}_8") (pintype "output"))
      (node (ref "E3") (pin "11") (pinfunction "I_11") (pintype "input"))
    )
    (net (code "61") (name "Net-(E3A-I)") (class "Default")
      (node (ref "E3") (pin "1") (pinfunction "I_1") (pintype "input"))
      (node (ref "E4") (pin "6") (pinfunction "~{Q}_6") (pintype "output"))
    )
    (net (code "62") (name "Net-(E3B-I)") (class "Default")
      (node (ref "E3") (pin "3") (pinfunction "I_3") (pintype "input"))
      (node (ref "E4") (pin "8") (pinfunction "~{Q}_8") (pintype "output"))
    )
    (net (code "63") (name "Net-(E6A-I)") (class "Default")
      (node (ref "E6") (pin "1") (pinfunction "I_1") (pintype "input"))
      (node (ref "E6") (pin "13") (pinfunction "I_13") (pintype "input"))
      (node (ref "E8") (pin "6") (pinfunction "O_6") (pintype "output"))
      (node (ref "E9") (pin "4") (pinfunction "PRE_4") (pintype "input"))
    )
    (net (code "64") (name "Net-(E6B-I)") (class "Default")
      (node (ref "E6") (pin "3") (pinfunction "I_3") (pintype "input"))
      (node (ref "E8") (pin "3") (pinfunction "O_3") (pintype "output"))
    )
    (net (code "65") (name "Net-(E6C-I)") (class "Default")
      (node (ref "E6") (pin "5") (pinfunction "I_5") (pintype "input"))
      (node (ref "E8") (pin "11") (pinfunction "O_11") (pintype "output"))
    )
    (net (code "66") (name "Net-(E6D-I)") (class "Default")
      (node (ref "E6") (pin "9") (pinfunction "I_9") (pintype "input"))
      (node (ref "E7") (pin "6") (pinfunction "~{Q}_6") (pintype "output"))
    )
    (net (code "67") (name "Net-(E6E-I)") (class "Default")
      (node (ref "E6") (pin "11") (pinfunction "I_11") (pintype "input"))
      (node (ref "E7") (pin "8") (pinfunction "~{Q}_8") (pintype "output"))
    )
    (net (code "68") (name "Net-(E8A-I0)") (class "Default")
      (node (ref "E8") (pin "1") (pinfunction "I0_1") (pintype "input"))
      (node (ref "E8") (pin "2") (pinfunction "I1_2") (pintype "input"))
      (node (ref "E8") (pin "8") (pinfunction "O_8") (pintype "output"))
    )
    (net (code "69") (name "Net-(E11A-O)") (class "Default")
      (node (ref "E11") (pin "8") (pinfunction "O_8") (pintype "output"))
      (node (ref "E14") (pin "12") (pinfunction "I0_12") (pintype "input"))
      (node (ref "E14") (pin "13") (pinfunction "I1_13") (pintype "input"))
    )
    (net (code "70") (name "Net-(E12A-I0)") (class "Default")
      (node (ref "E10") (pin "6") (pinfunction "6_6") (pintype "passive"))
      (node (ref "E12") (pin "2") (pinfunction "I0_2") (pintype "input"))
      (node (ref "E12") (pin "3") (pinfunction "I1_3") (pintype "input"))
      (node (ref "E12") (pin "5") (pinfunction "I0_5") (pintype "input"))
      (node (ref "E12") (pin "6") (pinfunction "I1_6") (pintype "input"))
      (node (ref "E16") (pin "10") (pinfunction "PRE_10") (pintype "input"))
      (node (ref "E9") (pin "3") (pinfunction "CLK_3") (pintype "input"))
    )
    (net (code "71") (name "Net-(E13A-I0)") (class "Default")
      (node (ref "E13") (pin "1") (pinfunction "I0_1") (pintype "input"))
      (node (ref "E16") (pin "9") (pinfunction "Q_9") (pintype "output"))
    )
    (net (code "72") (name "Net-(E13A-I1)") (class "Default")
      (node (ref "E13") (pin "2") (pinfunction "I1_2") (pintype "input"))
      (node (ref "E13") (pin "4") (pinfunction "I2_4") (pintype "input"))
      (node (ref "E13") (pin "5") (pinfunction "I3_5") (pintype "input"))
      (node (ref "E14") (pin "8") (pinfunction "O_8") (pintype "output"))
    )
    (net (code "73") (name "Net-(E14A-I1)") (class "Default")
      (node (ref "E14") (pin "2") (pinfunction "I1_2") (pintype "input"))
      (node (ref "E14") (pin "6") (pinfunction "O_6") (pintype "output"))
      (node (ref "E5") (pin "3") (pinfunction "3_3") (pintype "passive"))
      (node (ref "E5") (pin "4") (pinfunction "4_4") (pintype "passive"))
    )
    (net (code "74") (name "Net-(E14A-O)") (class "Default")
      (node (ref "E14") (pin "3") (pinfunction "O_3") (pintype "output"))
      (node (ref "E16") (pin "12") (pinfunction "D_12") (pintype "input"))
    )
    (net (code "75") (name "Net-(E14D-O)") (class "Default")
      (node (ref "E14") (pin "11") (pinfunction "O_11") (pintype "output"))
      (node (ref "E8") (pin "10") (pinfunction "I1_10") (pintype "input"))
      (node (ref "E8") (pin "13") (pinfunction "I1_13") (pintype "input"))
      (node (ref "E8") (pin "5") (pinfunction "I1_5") (pintype "input"))
    )
    (net (code "76") (name "Net-(E16A-CLK)") (class "Default")
      (node (ref "E15") (pin "6") (pinfunction "6_6") (pintype "passive"))
      (node (ref "E16") (pin "3") (pinfunction "CLK_3") (pintype "input"))
    )
    (net (code "77") (name "Net-(E16A-D)") (class "Default")
      (node (ref "E1") (pin "10") (pinfunction "PRE_10") (pintype "input"))
      (node (ref "E1") (pin "4") (pinfunction "PRE_4") (pintype "input"))
      (node (ref "E16") (pin "13") (pinfunction "CLR_13") (pintype "input"))
      (node (ref "E16") (pin "2") (pinfunction "D_2") (pintype "input"))
      (node (ref "E16") (pin "4") (pinfunction "PRE_4") (pintype "input"))
      (node (ref "E2") (pin "10") (pinfunction "PRE_10") (pintype "input"))
      (node (ref "E2") (pin "4") (pinfunction "PRE_4") (pintype "input"))
      (node (ref "E4") (pin "10") (pinfunction "PRE_10") (pintype "input"))
      (node (ref "E4") (pin "4") (pinfunction "PRE_4") (pintype "input"))
      (node (ref "E7") (pin "10") (pinfunction "PRE_10") (pintype "input"))
      (node (ref "E7") (pin "4") (pinfunction "PRE_4") (pintype "input"))
      (node (ref "E9") (pin "10") (pinfunction "PRE_10") (pintype "input"))
      (node (ref "E9") (pin "12") (pinfunction "D_12") (pintype "input"))
      (node (ref "R5") (pin "1") (pinfunction "1_1") (pintype "passive"))
    )
    (net (code "78") (name "Net-(E16B-~{Q})") (class "Default")
      (node (ref "E10") (pin "3") (pinfunction "3_3") (pintype "passive"))
      (node (ref "E10") (pin "4") (pinfunction "4_4") (pintype "passive"))
      (node (ref "E16") (pin "8") (pinfunction "~{Q}_8") (pintype "output"))
    )
    (net (code "79") (name "Net-(Q1-B)") (class "Default")
      (node (ref "C26") (pin "1") (pinfunction "1_1") (pintype "passive"))
      (node (ref "Q1") (pin "2") (pinfunction "B_2") (pintype "passive"))
      (node (ref "R4") (pin "2") (pinfunction "2_2") (pintype "passive"))
    )
    (net (code "80") (name "Net-(Q1-C)") (class "Default")
      (node (ref "Q1") (pin "1") (pinfunction "C_1") (pintype "passive"))
      (node (ref "Q2") (pin "2") (pinfunction "B_2") (pintype "passive"))
      (node (ref "R2") (pin "1") (pinfunction "1_1") (pintype "passive"))
      (node (ref "R6") (pin "2") (pinfunction "2_2") (pintype "passive"))
    )
    (net (code "81") (name "Net-(Q1-E)") (class "Default")
      (node (ref "Q1") (pin "3") (pinfunction "E_3") (pintype "passive"))
      (node (ref "Q2") (pin "3") (pinfunction "E_3") (pintype "passive"))
      (node (ref "R1") (pin "1") (pinfunction "1_1") (pintype "passive"))
    )
    (net (code "82") (name "Net-(U$2A-1)") (class "Default")
      (node (ref "U$2") (pin "AA1") (pinfunction "1_AA1") (pintype "bidirectional"))
      (node (ref "U$7") (pin "A1") (pinfunction "P$1_A1") (pintype "passive"))
    )
    (net (code "83") (name "Net-(U$2AI-1)") (class "Default")
      (node (ref "U$2") (pin "AV1") (pinfunction "1_AV1") (pintype "bidirectional"))
      (node (ref "U$7") (pin "V1") (pinfunction "P$1_V1") (pintype "passive"))
    )
    (net (code "84") (name "Net-(U$2AK-1)") (class "Default")
      (node (ref "U$2") (pin "BA1") (pinfunction "1_BA1") (pintype "bidirectional"))
      (node (ref "U$5") (pin "A1") (pinfunction "P$1_A1") (pintype "passive"))
    )
    (net (code "85") (name "Net-(U$2AM-1)") (class "Default")
      (node (ref "U$2") (pin "BB1") (pinfunction "1_BB1") (pintype "bidirectional"))
      (node (ref "U$5") (pin "B1") (pinfunction "P$1_B1") (pintype "passive"))
    )
    (net (code "86") (name "Net-(U$2AN-1)") (class "Default")
      (node (ref "U$2") (pin "BB2") (pinfunction "1_BB2") (pintype "bidirectional"))
      (node (ref "U$5") (pin "B2") (pinfunction "P$1_B2") (pintype "passive"))
    )
    (net (code "87") (name "Net-(U$2AO-1)") (class "Default")
      (node (ref "U$2") (pin "BC1") (pinfunction "1_BC1") (pintype "bidirectional"))
      (node (ref "U$5") (pin "C1") (pinfunction "P$1_C1") (pintype "passive"))
    )
    (net (code "88") (name "Net-(U$2AW-1)") (class "Default")
      (node (ref "U$2") (pin "BH1") (pinfunction "1_BH1") (pintype "bidirectional"))
      (node (ref "U$5") (pin "H1") (pinfunction "P$1_H1") (pintype "passive"))
    )
    (net (code "89") (name "Net-(U$2AY-1)") (class "Default")
      (node (ref "U$2") (pin "BJ1") (pinfunction "1_BJ1") (pintype "bidirectional"))
      (node (ref "U$5") (pin "J1") (pinfunction "P$1_J1") (pintype "passive"))
    )
    (net (code "90") (name "Net-(U$2BB-1)") (class "Default")
      (node (ref "U$2") (pin "BK2") (pinfunction "1_BK2") (pintype "bidirectional"))
      (node (ref "U$5") (pin "K2") (pinfunction "P$1_K2") (pintype "passive"))
    )
    (net (code "91") (name "Net-(U$2BD-1)") (class "Default")
      (node (ref "U$2") (pin "BL2") (pinfunction "1_BL2") (pintype "bidirectional"))
      (node (ref "U$5") (pin "L2") (pinfunction "P$1_L2") (pintype "passive"))
    )
    (net (code "92") (name "Net-(U$2BF-1)") (class "Default")
      (node (ref "U$2") (pin "BM2") (pinfunction "1_BM2") (pintype "bidirectional"))
      (node (ref "U$5") (pin "M2") (pinfunction "P$1_M2") (pintype "passive"))
    )
    (net (code "93") (name "Net-(U$2BG-1)") (class "Default")
      (node (ref "U$2") (pin "BN1") (pinfunction "1_BN1") (pintype "bidirectional"))
      (node (ref "U$5") (pin "N1") (pinfunction "P$1_N1") (pintype "passive"))
    )
    (net (code "94") (name "Net-(U$2BI-1)") (class "Default")
      (node (ref "U$2") (pin "BP1") (pinfunction "1_BP1") (pintype "bidirectional"))
      (node (ref "U$5") (pin "P1") (pinfunction "P$1_P1") (pintype "passive"))
    )
    (net (code "95") (name "Net-(U$2BJ-1)") (class "Default")
      (node (ref "U$2") (pin "BP2") (pinfunction "1_BP2") (pintype "bidirectional"))
      (node (ref "U$5") (pin "P2") (pinfunction "P$1_P2") (pintype "passive"))
    )
    (net (code "96") (name "Net-(U$2BK-1)") (class "Default")
      (node (ref "U$2") (pin "BR1") (pinfunction "1_BR1") (pintype "bidirectional"))
      (node (ref "U$5") (pin "R1") (pinfunction "P$1_R1") (pintype "passive"))
    )
    (net (code "97") (name "Net-(U$2BL-1)") (class "Default")
      (node (ref "U$2") (pin "BR2") (pinfunction "1_BR2") (pintype "bidirectional"))
      (node (ref "U$5") (pin "R2") (pinfunction "P$1_R2") (pintype "passive"))
    )
    (net (code "98") (name "Net-(U$2BM-1)") (class "Default")
      (node (ref "U$2") (pin "BS1") (pinfunction "1_BS1") (pintype "bidirectional"))
      (node (ref "U$5") (pin "S1") (pinfunction "P$1_S1") (pintype "passive"))
    )
    (net (code "99") (name "Net-(U$2BP-1)") (class "Default")
      (node (ref "U$2") (pin "BT2") (pinfunction "1_BT2") (pintype "bidirectional"))
      (node (ref "U$5") (pin "T2") (pinfunction "P$1_T2") (pintype "passive"))
    )
    (net (code "100") (name "Net-(U$2BT-1)") (class "Default")
      (node (ref "U$2") (pin "BV2") (pinfunction "1_BV2") (pintype "bidirectional"))
      (node (ref "U$5") (pin "V2") (pinfunction "P$1_V2") (pintype "passive"))
    )
    (net (code "101") (name "Net-(U$2C-1)") (class "Default")
      (node (ref "U$2") (pin "AB1") (pinfunction "1_AB1") (pintype "bidirectional"))
      (node (ref "U$7") (pin "B1") (pinfunction "P$1_B1") (pintype "passive"))
    )
    (net (code "102") (name "Net-(U$2D-1)") (class "Default")
      (node (ref "U$2") (pin "AB2") (pinfunction "1_AB2") (pintype "bidirectional"))
      (node (ref "U$7") (pin "B2") (pinfunction "P$1_B2") (pintype "passive"))
    )
    (net (code "103") (name "Net-(U$2E-1)") (class "Default")
      (node (ref "U$2") (pin "AC1") (pinfunction "1_AC1") (pintype "bidirectional"))
      (node (ref "U$7") (pin "C1") (pinfunction "P$1_C1") (pintype "passive"))
    )
    (net (code "104") (name "VCC") (class "Default")
      (node (ref "C1") (pin "1") (pinfunction "1_1") (pintype "passive"))
      (node (ref "C10") (pin "1") (pinfunction "1_1") (pintype "passive"))
      (node (ref "C11") (pin "1") (pinfunction "1_1") (pintype "passive"))
      (node (ref "C12") (pin "1") (pinfunction "1_1") (pintype "passive"))
      (node (ref "C13") (pin "1") (pinfunction "1_1") (pintype "passive"))
      (node (ref "C14") (pin "1") (pinfunction "1_1") (pintype "passive"))
      (node (ref "C15") (pin "1") (pinfunction "1_1") (pintype "passive"))
      (node (ref "C16") (pin "1") (pinfunction "1_1") (pintype "passive"))
      (node (ref "C17") (pin "1") (pinfunction "1_1") (pintype "passive"))
      (node (ref "C18") (pin "1") (pinfunction "1_1") (pintype "passive"))
      (node (ref "C19") (pin "1") (pinfunction "1_1") (pintype "passive"))
      (node (ref "C2") (pin "1") (pinfunction "1_1") (pintype "passive"))
      (node (ref "C20") (pin "1") (pinfunction "1_1") (pintype "passive"))
      (node (ref "C21") (pin "1") (pinfunction "1_1") (pintype "passive"))
      (node (ref "C3") (pin "1") (pinfunction "1_1") (pintype "passive"))
      (node (ref "C4") (pin "1") (pinfunction "1_1") (pintype "passive"))
      (node (ref "C5") (pin "1") (pinfunction "1_1") (pintype "passive"))
      (node (ref "C6") (pin "1") (pinfunction "1_1") (pintype "passive"))
      (node (ref "C7") (pin "1") (pinfunction "1_1") (pintype "passive"))
      (node (ref "C8") (pin "1") (pinfunction "1_1") (pintype "passive"))
      (node (ref "C9") (pin "1") (pinfunction "1_1") (pintype "passive"))
      (node (ref "E10") (pin "14") (pinfunction "14_14") (pintype "passive"))
      (node (ref "E15") (pin "14") (pinfunction "14_14") (pintype "passive"))
      (node (ref "E5") (pin "14") (pinfunction "14_14") (pintype "passive"))
      (node (ref "R1") (pin "2") (pinfunction "2_2") (pintype "passive"))
      (node (ref "R10") (pin "2") (pinfunction "2_2") (pintype "passive"))
      (node (ref "R11") (pin "2") (pinfunction "2_2") (pintype "passive"))
      (node (ref "R13") (pin "2") (pinfunction "2_2") (pintype "passive"))
      (node (ref "R14") (pin "2") (pinfunction "2_2") (pintype "passive"))
      (node (ref "R2") (pin "2") (pinfunction "2_2") (pintype "passive"))
      (node (ref "R3") (pin "2") (pinfunction "2_2") (pintype "passive"))
      (node (ref "R5") (pin "2") (pinfunction "2_2") (pintype "passive"))
      (node (ref "R8") (pin "2") (pinfunction "2_2") (pintype "passive"))
      (node (ref "R9") (pin "2") (pinfunction "2_2") (pintype "passive"))
      (node (ref "U$2") (pin "AA2") (pinfunction "1_AA2") (pintype "bidirectional"))
      (node (ref "U$2") (pin "BA2") (pinfunction "1_BA2") (pintype "bidirectional"))
      (node (ref "U$5") (pin "A2") (pinfunction "P$1_A2") (pintype "passive"))
      (node (ref "U$7") (pin "A2") (pinfunction "P$1_A2") (pintype "passive"))
    )
    (net (code "105") (name "unconnected-(E1A-Q-Pad5)") (class "Default")
      (node (ref "E1") (pin "5") (pinfunction "Q_5") (pintype "output"))
    )
    (net (code "106") (name "unconnected-(E1B-Q-Pad9)") (class "Default")
      (node (ref "E1") (pin "9") (pinfunction "Q_9") (pintype "output"))
    )
    (net (code "107") (name "unconnected-(E2A-Q-Pad5)") (class "Default")
      (node (ref "E2") (pin "5") (pinfunction "Q_5") (pintype "output"))
    )
    (net (code "108") (name "unconnected-(E2B-Q-Pad9)") (class "Default")
      (node (ref "E2") (pin "9") (pinfunction "Q_9") (pintype "output"))
    )
    (net (code "109") (name "unconnected-(E4A-Q-Pad5)") (class "Default")
      (node (ref "E4") (pin "5") (pinfunction "Q_5") (pintype "output"))
    )
    (net (code "110") (name "unconnected-(E4B-Q-Pad9)") (class "Default")
      (node (ref "E4") (pin "9") (pinfunction "Q_9") (pintype "output"))
    )
    (net (code "111") (name "unconnected-(E5-Pad5)") (class "Default")
      (node (ref "E5") (pin "5") (pinfunction "5_5") (pintype "passive"))
    )
    (net (code "112") (name "unconnected-(E5-Pad6)") (class "Default")
      (node (ref "E5") (pin "6") (pinfunction "6_6") (pintype "passive"))
    )
    (net (code "113") (name "unconnected-(E5-Pad9)") (class "Default")
      (node (ref "E5") (pin "9") (pinfunction "9_9") (pintype "passive"))
    )
    (net (code "114") (name "unconnected-(E5-Pad10)") (class "Default")
      (node (ref "E5") (pin "10") (pinfunction "10_10") (pintype "passive"))
    )
    (net (code "115") (name "unconnected-(E5-Pad12)") (class "Default")
      (node (ref "E5") (pin "12") (pinfunction "12_12") (pintype "passive"))
    )
    (net (code "116") (name "unconnected-(E7A-Q-Pad5)") (class "Default")
      (node (ref "E7") (pin "5") (pinfunction "Q_5") (pintype "output"))
    )
    (net (code "117") (name "unconnected-(E7B-Q-Pad9)") (class "Default")
      (node (ref "E7") (pin "9") (pinfunction "Q_9") (pintype "output"))
    )
    (net (code "118") (name "unconnected-(E9A-Q-Pad5)") (class "Default")
      (node (ref "E9") (pin "5") (pinfunction "Q_5") (pintype "output"))
    )
    (net (code "119") (name "unconnected-(E9B-~{Q}-Pad8)") (class "Default")
      (node (ref "E9") (pin "8") (pinfunction "~{Q}_8") (pintype "output"))
    )
    (net (code "120") (name "unconnected-(E10-Pad5)") (class "Default")
      (node (ref "E10") (pin "5") (pinfunction "5_5") (pintype "passive"))
    )
    (net (code "121") (name "unconnected-(E10-Pad8)") (class "Default")
      (node (ref "E10") (pin "8") (pinfunction "8_8") (pintype "passive"))
    )
    (net (code "122") (name "unconnected-(E10-Pad9)") (class "Default")
      (node (ref "E10") (pin "9") (pinfunction "9_9") (pintype "passive"))
    )
    (net (code "123") (name "unconnected-(E10-Pad10)") (class "Default")
      (node (ref "E10") (pin "10") (pinfunction "10_10") (pintype "passive"))
    )
    (net (code "124") (name "unconnected-(E10-Pad12)") (class "Default")
      (node (ref "E10") (pin "12") (pinfunction "12_12") (pintype "passive"))
    )
    (net (code "125") (name "unconnected-(E15-Pad5)") (class "Default")
      (node (ref "E15") (pin "5") (pinfunction "5_5") (pintype "passive"))
    )
    (net (code "126") (name "unconnected-(E15-Pad8)") (class "Default")
      (node (ref "E15") (pin "8") (pinfunction "8_8") (pintype "passive"))
    )
    (net (code "127") (name "unconnected-(E15-Pad9)") (class "Default")
      (node (ref "E15") (pin "9") (pinfunction "9_9") (pintype "passive"))
    )
    (net (code "128") (name "unconnected-(E15-Pad10)") (class "Default")
      (node (ref "E15") (pin "10") (pinfunction "10_10") (pintype "passive"))
    )
    (net (code "129") (name "unconnected-(E15-Pad12)") (class "Default")
      (node (ref "E15") (pin "12") (pinfunction "12_12") (pintype "passive"))
    )
    (net (code "130") (name "unconnected-(E16A-~{Q}-Pad6)") (class "Default")
      (node (ref "E16") (pin "6") (pinfunction "~{Q}_6") (pintype "output"))
    )
  )
)
